# 04__EFR32_Signal_Assign.net
KiCad netlist of a schematic drawn in Altium Designer
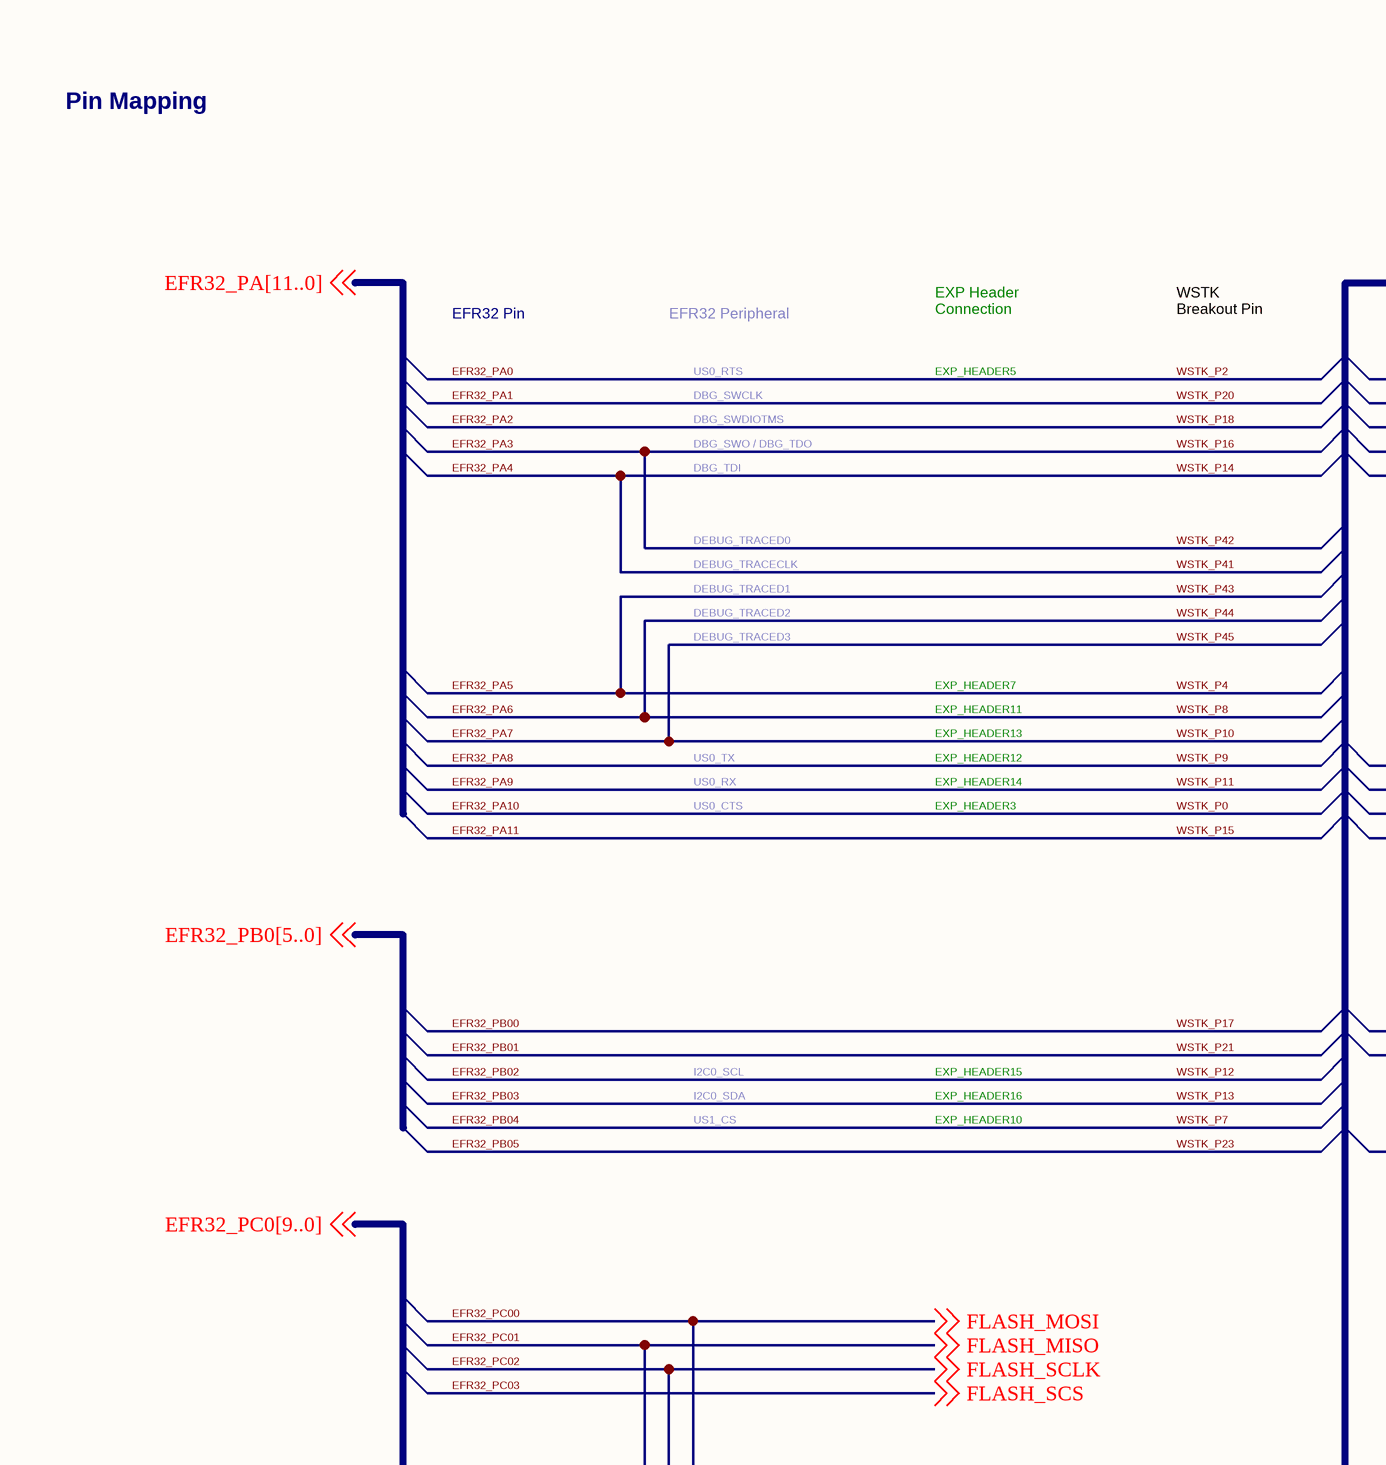
[diagram p0: 04_ EFR32 Signal Assign.SchDoc, top left]
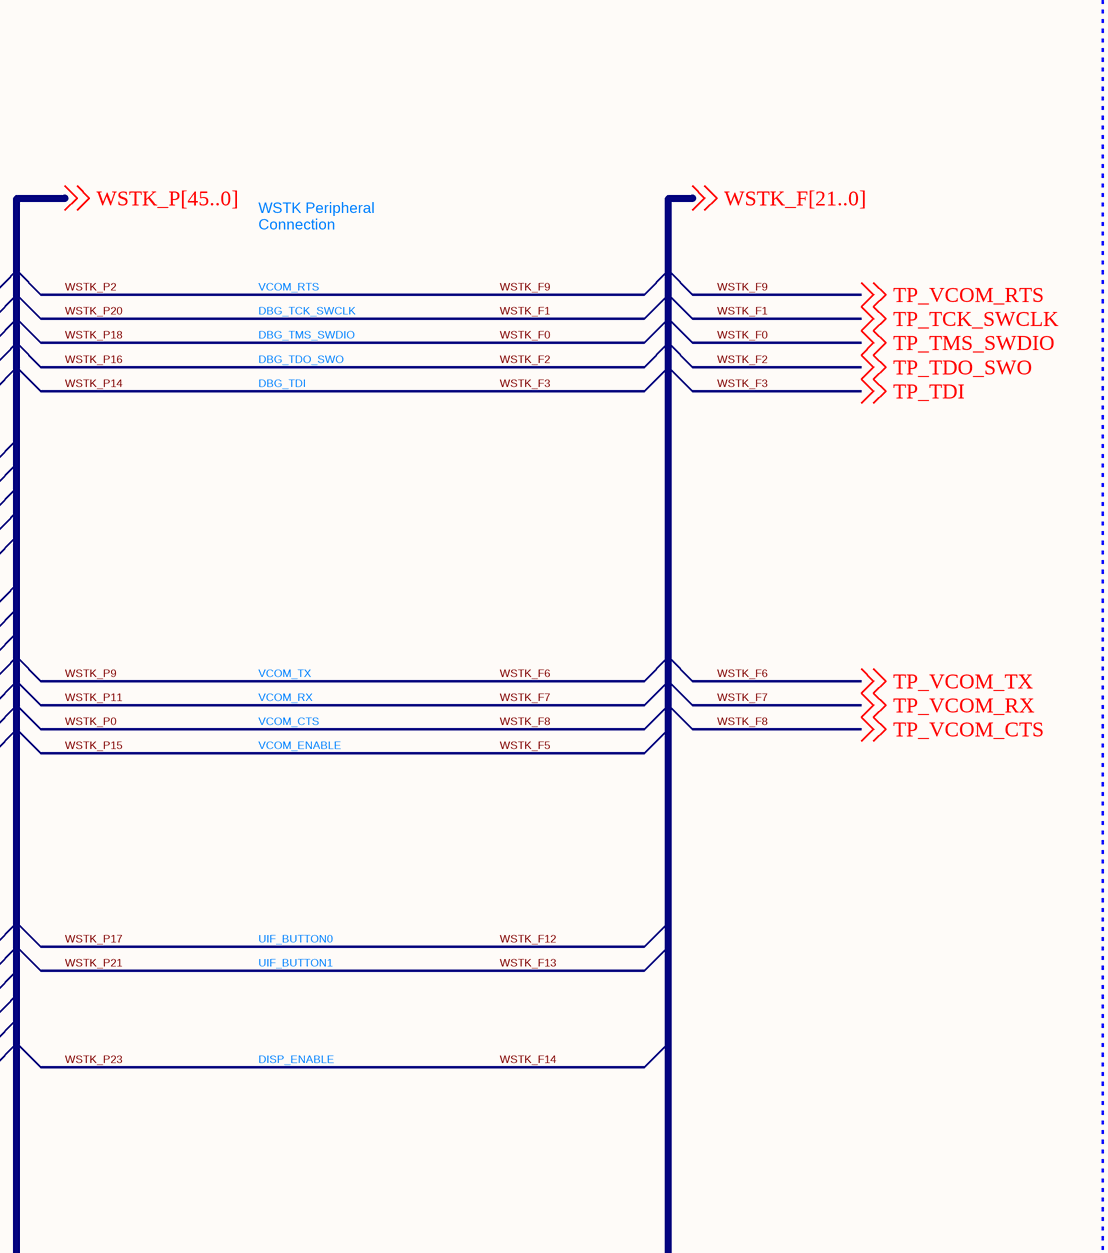
[diagram p1: 04_ EFR32 Signal Assign.SchDoc, top middle]
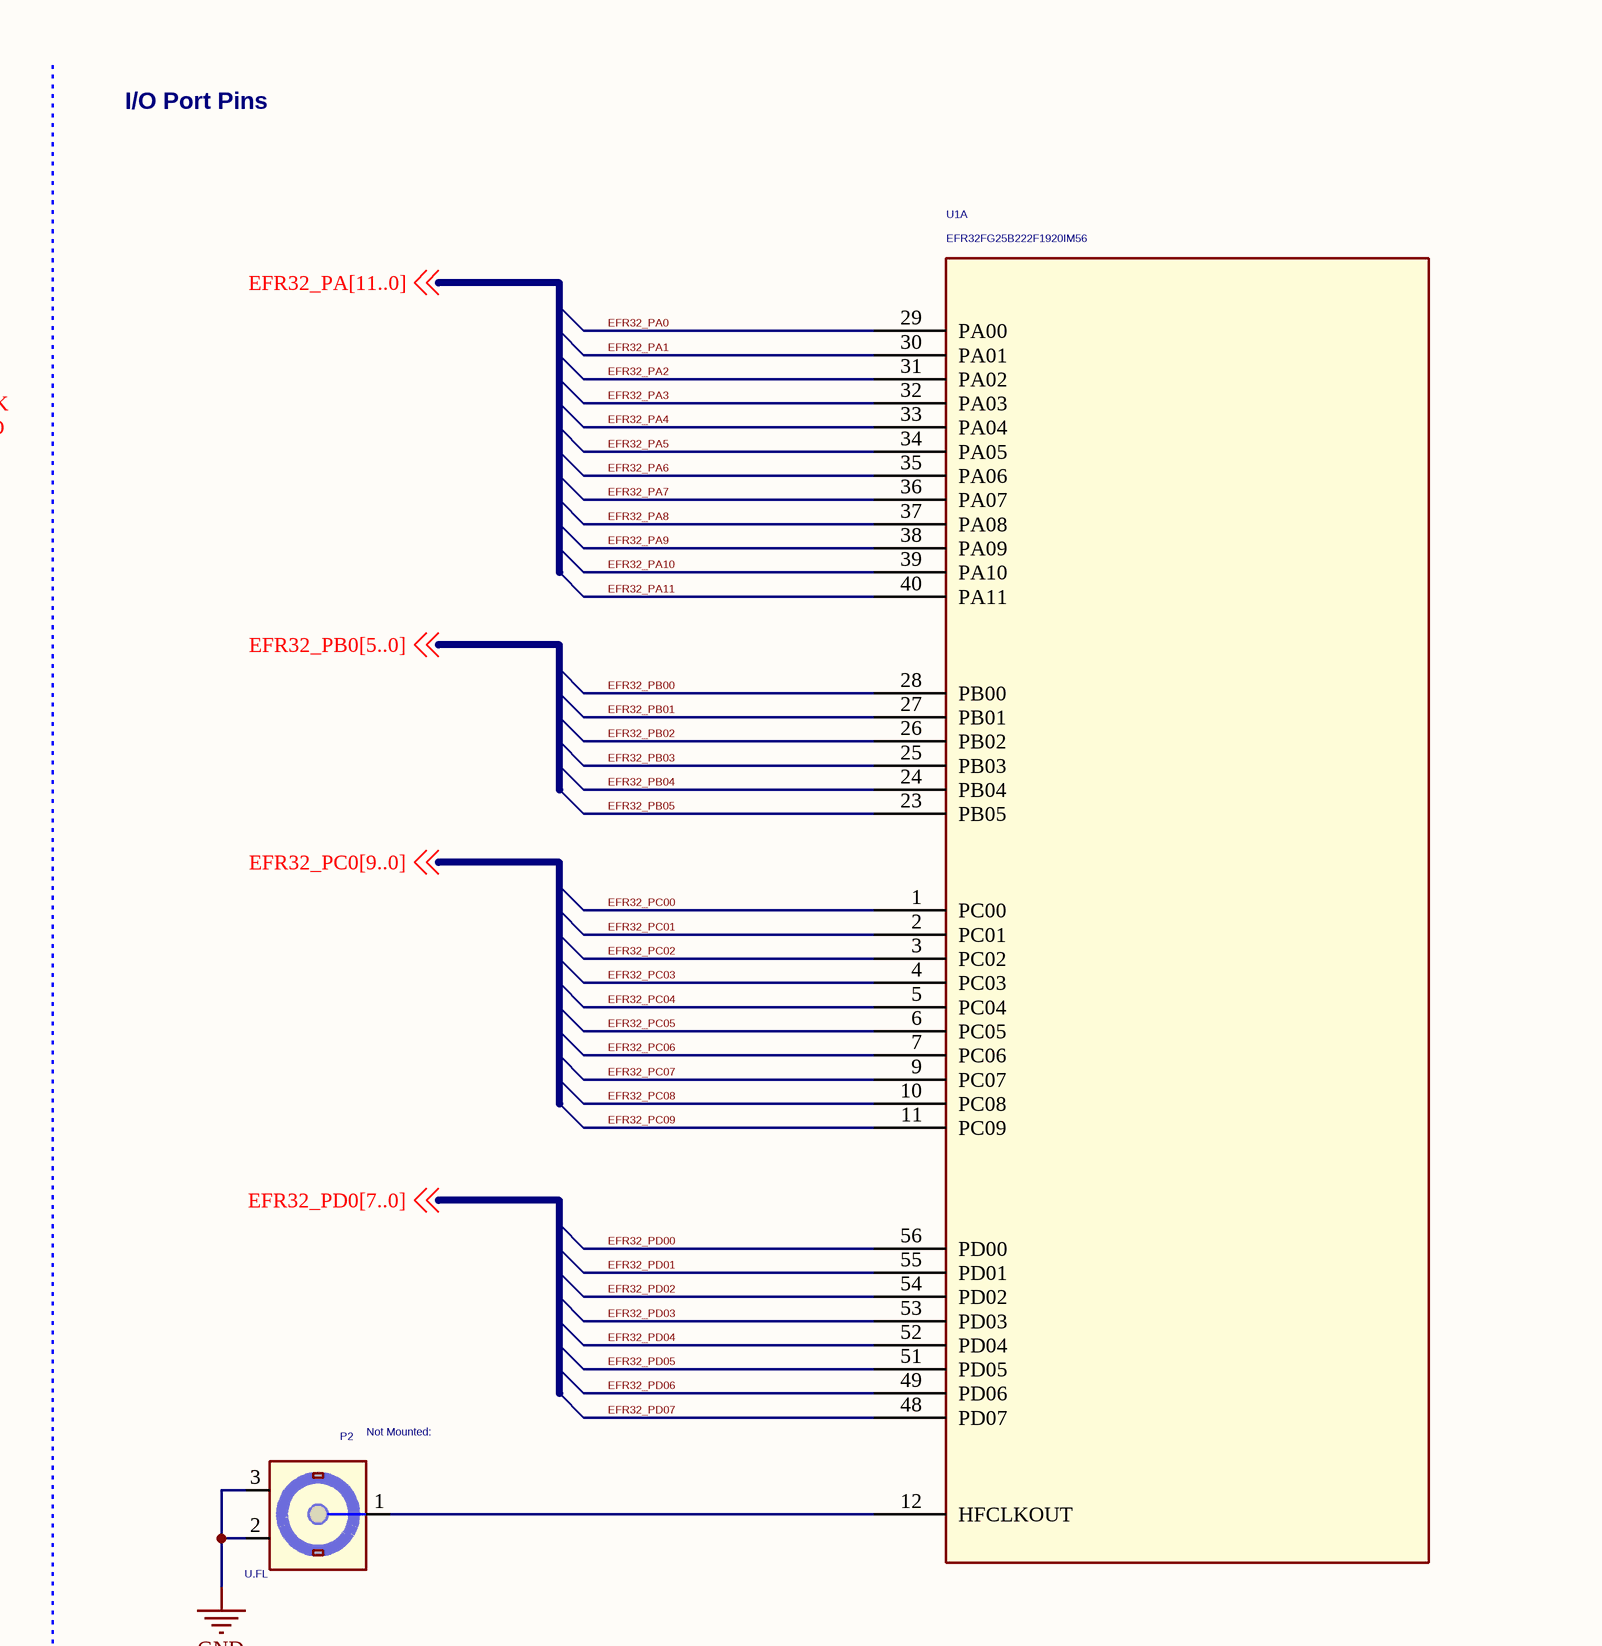
[diagram p2: 04_ EFR32 Signal Assign.SchDoc, top right]
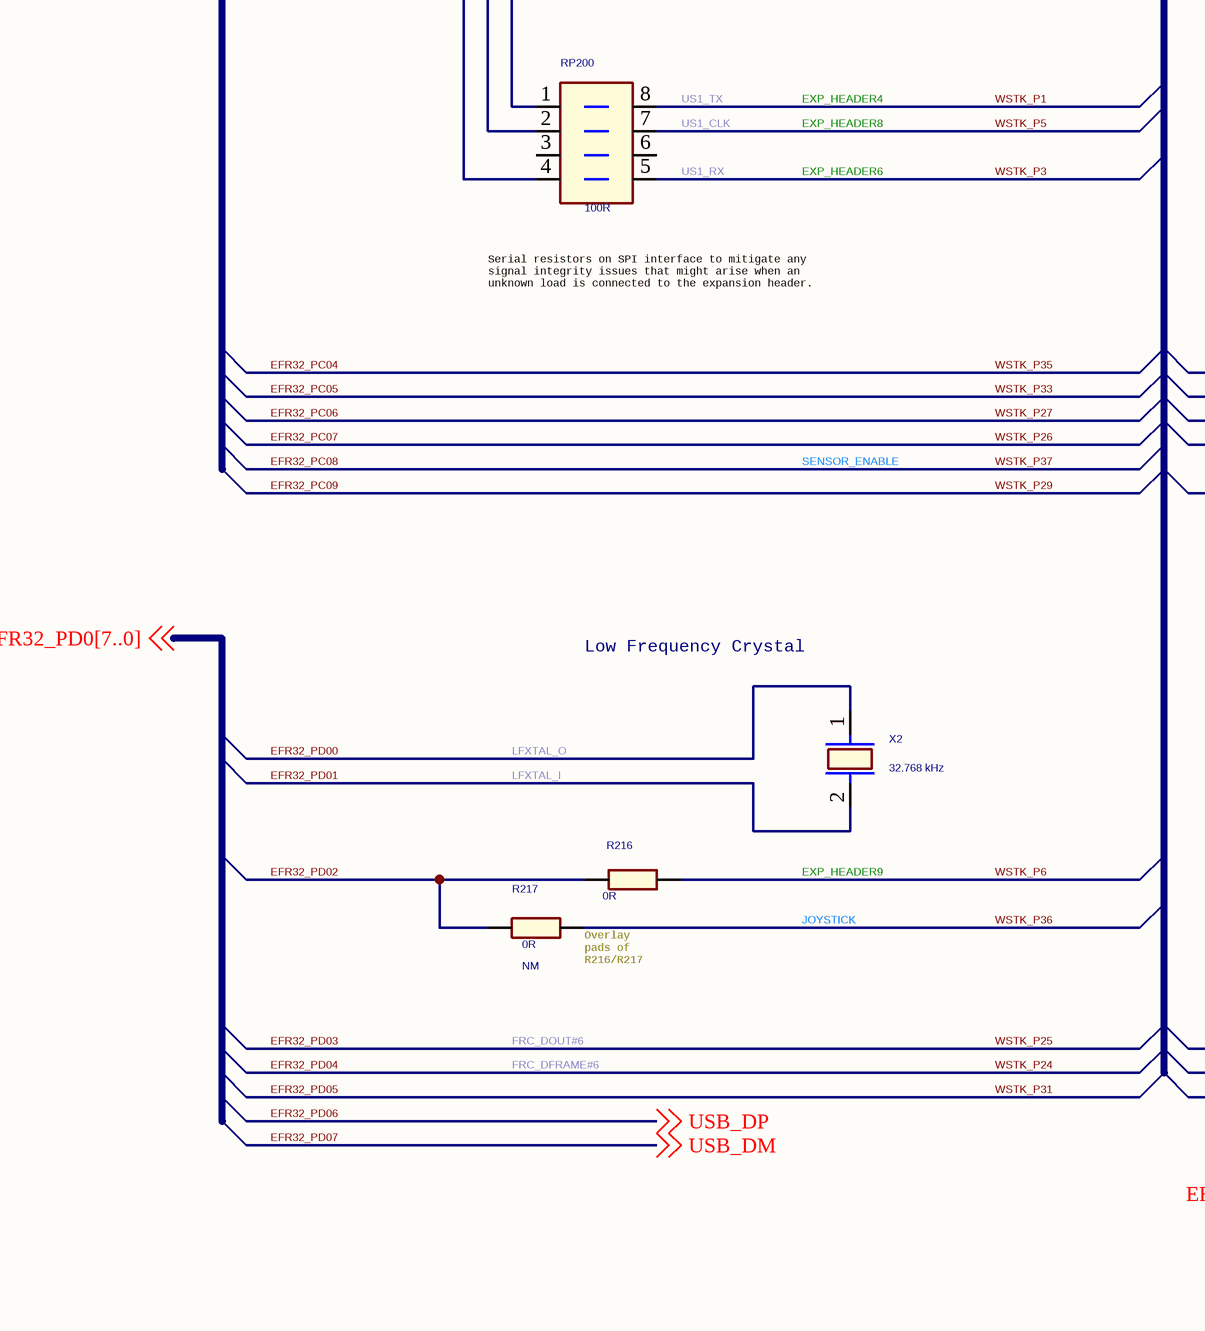
[diagram p3: 04_ EFR32 Signal Assign.SchDoc, bottom left]
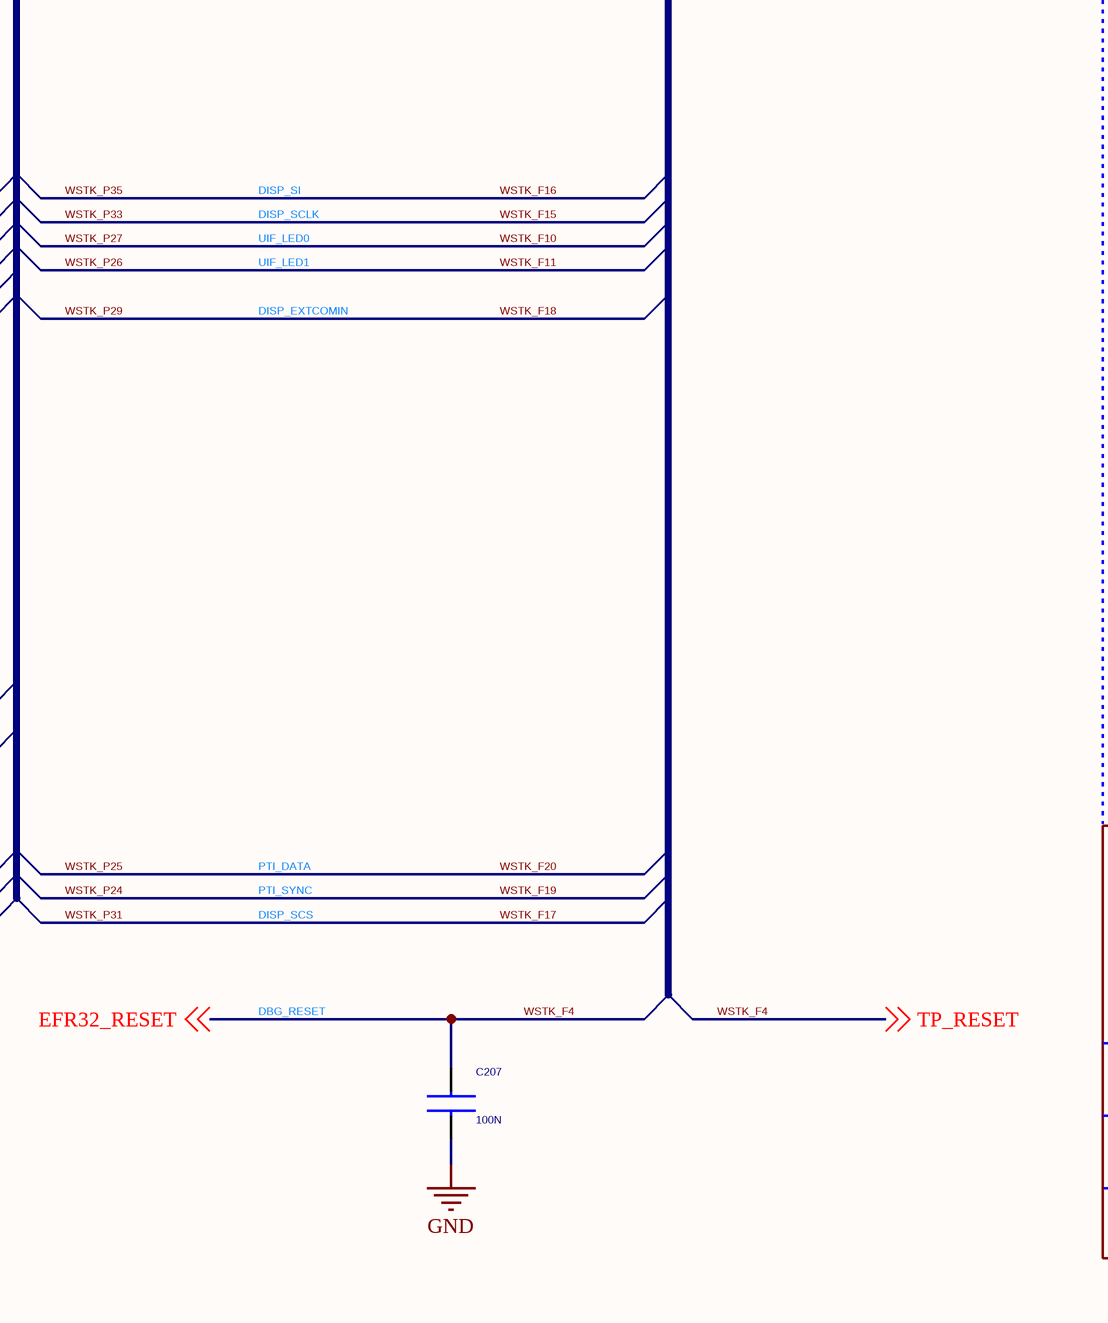
[diagram p4: 04_ EFR32 Signal Assign.SchDoc, bottom middle]
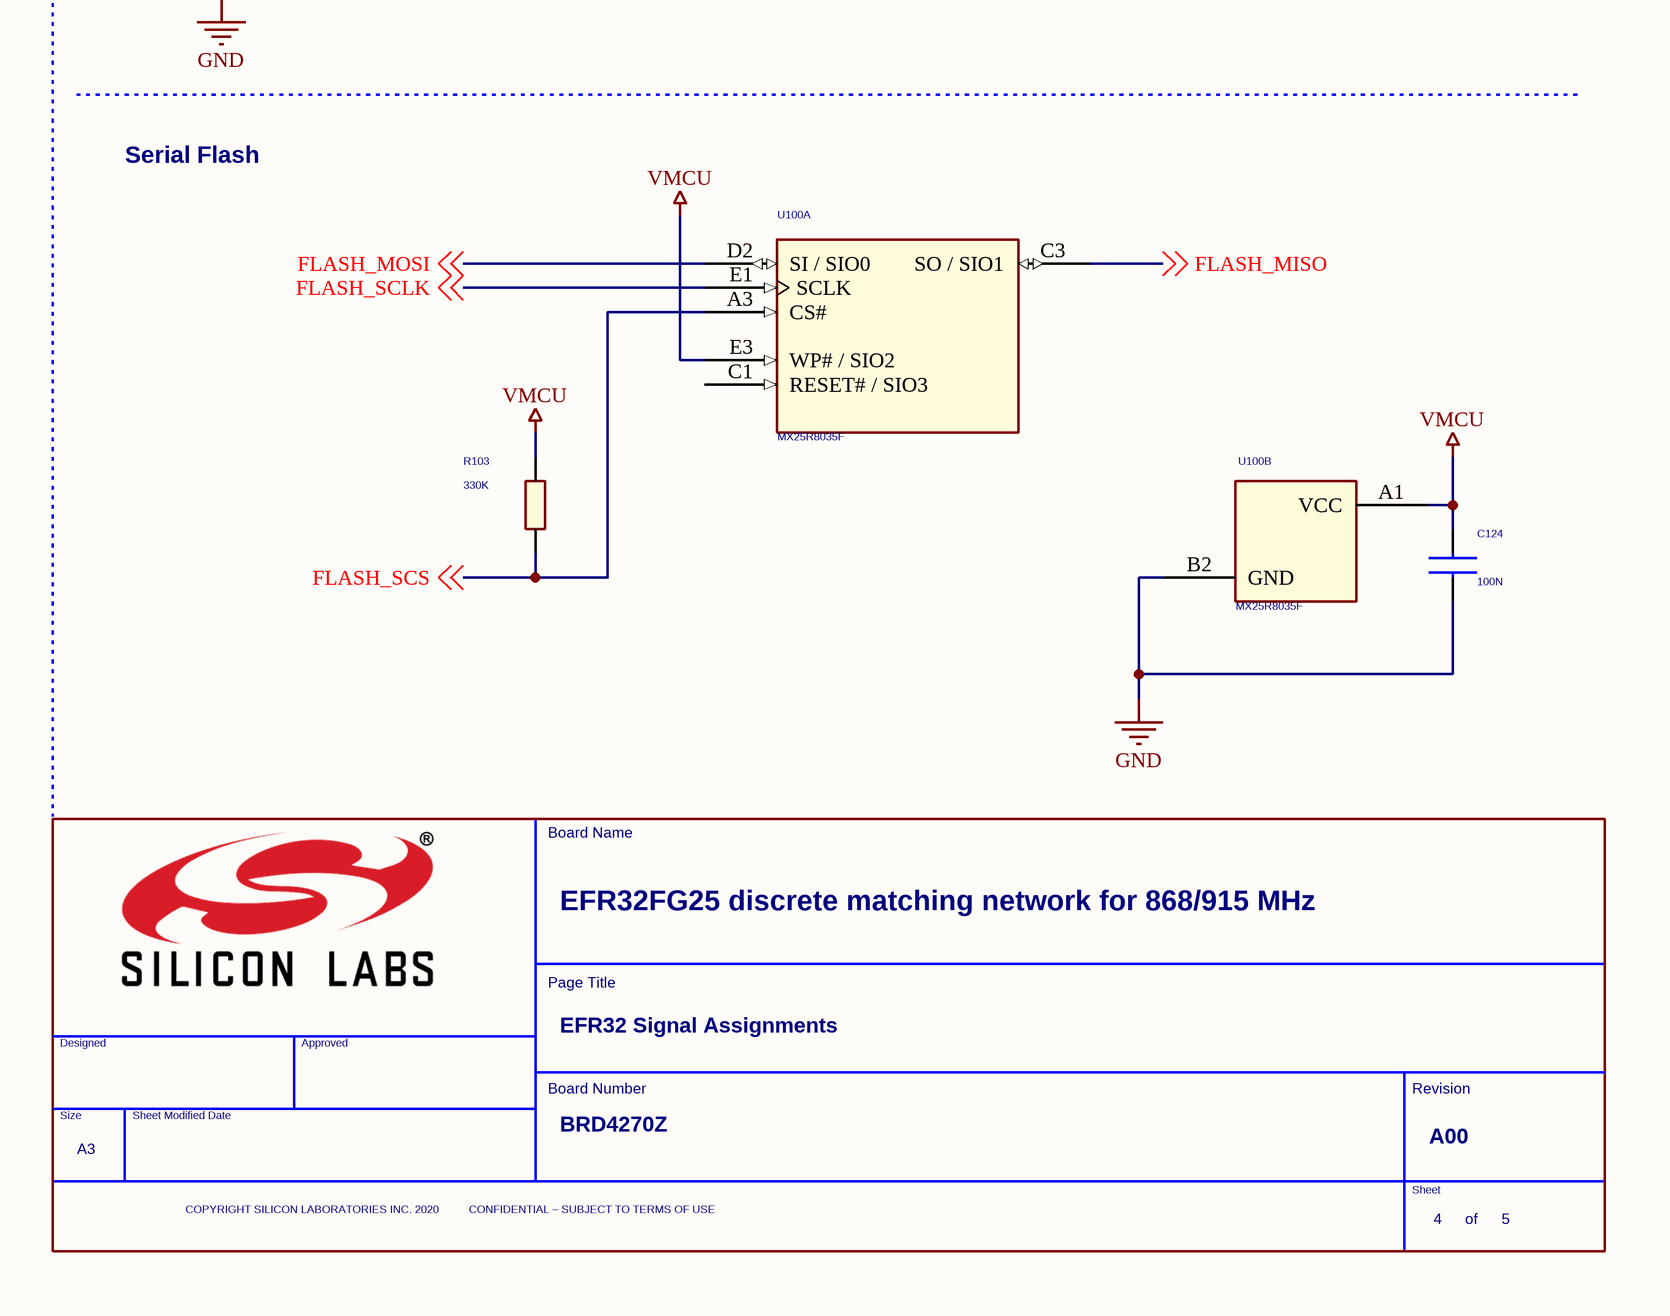
[diagram p5: 04_ EFR32 Signal Assign.SchDoc, bottom right]

(export (version "E")
  (design (tool "Eeschema 10.0.6"))
  (components
    (comp (ref "C124")
      (value "100N")
      (footprint "C0201_L")
      (fields (field (name "TOLERANCE") "20%"))
      (libsource (lib "*") (part "C0201"))
    )
    (comp (ref "C207")
      (value "100N")
      (footprint "C0201_L")
      (fields (field (name "TOLERANCE") "20%"))
      (libsource (lib "*") (part "C0201"))
    )
    (comp (ref "P2")
      (value "U.FL")
      (footprint "HIROSE_U.FL-R-SMT-1")
      (fields (field (name "MFG") "KLS"))
      (libsource (lib "*") (part "KLS_U.FL"))
    )
    (comp (ref "R103") (value "330K") (footprint "R0201_L") (libsource (lib "*") (part "R0201")))
    (comp (ref "R216") (value "0R") (footprint "R0402_L") (libsource (lib "") (part "R0402_1")))
    (comp (ref "R217")
      (value "0R")
      (footprint "R0402_L")
      (fields (field (name "NOT MOUNTED") "NM"))
      (libsource (lib "*") (part "R0402"))
    )
    (comp (ref "RP200")
      (value "100R")
      (footprint "RES_MNR04-8")
      (fields (field (name "MFG") "ROHM"))
      (libsource (lib "*") (part "MNR04M0APJ101"))
    )
    (comp (ref "U1")
      (value "EFR32FG25B222F1920IM56")
      (footprint "QFN56_M040_7.0X7.0_EP_SL")
      (fields (field (name "MFG") "Silicon Labs"))
      (libsource (lib "*") (part "EFR32xG25_QFN56_HFCLKOUT"))
    )
    (comp (ref "U100")
      (value "MX25R8035F")
      (footprint "BGA8_M040_1.24x1.75_WLCSP")
      (fields (field (name "MFG") "Macronix"))
      (libsource (lib "*") (part "MX25R8035"))
    )
    (comp (ref "X2")
      (value "32.768 kHz")
      (footprint "X_MCS_CM8V-T1A")
      (fields (field (name "MFG") "Micro Crystal AG"))
      (libsource (lib "*") (part "CM8V-T1A"))
    )
  )
  (nets
    (net (code "4") (name "EFR32_PD00") (class "Default")
      (node (ref "U1") (pin "56") (pinfunction "PD00_56") (pintype "passive"))
      (node (ref "X2") (pin "1") (pinfunction "1_1") (pintype "passive"))
    )
    (net (code "6") (name "EFR32_PD01") (class "Default")
      (node (ref "U1") (pin "55") (pinfunction "PD01_55") (pintype "passive"))
      (node (ref "X2") (pin "2") (pinfunction "2_2") (pintype "passive"))
    )
    (net (code "7") (name "EFR32_PD02") (class "Default")
      (node (ref "R216") (pin "2") (pinfunction "2_2") (pintype "passive"))
      (node (ref "R217") (pin "1") (pinfunction "1_1") (pintype "passive"))
      (node (ref "U1") (pin "54") (pinfunction "PD02_54") (pintype "passive"))
    )
    (net (code "8") (name "EFR32_PD03") (class "Default")
      (node (ref "U1") (pin "53") (pinfunction "PD03_53") (pintype "passive"))
    )
    (net (code "9") (name "EFR32_PD04") (class "Default")
      (node (ref "U1") (pin "52") (pinfunction "PD04_52") (pintype "passive"))
    )
    (net (code "10") (name "EFR32_PD05") (class "Default")
      (node (ref "U1") (pin "51") (pinfunction "PD05_51") (pintype "passive"))
    )
    (net (code "11") (name "EFR32_RESET") (class "Default")
      (node (ref "C207") (pin "1") (pinfunction "1_1") (pintype "passive"))
    )
    (net (code "12") (name "FLASH_MISO") (class "Default")
      (node (ref "RP200") (pin "4") (pinfunction "R14_4") (pintype "passive"))
      (node (ref "U1") (pin "2") (pinfunction "PC01_2") (pintype "passive"))
      (node (ref "U100") (pin "C3") (pinfunction "SO_/_SIO1_C3") (pintype "bidirectional"))
    )
    (net (code "13") (name "FLASH_MOSI") (class "Default")
      (node (ref "RP200") (pin "1") (pinfunction "R11_1") (pintype "passive"))
      (node (ref "U1") (pin "1") (pinfunction "PC00_1") (pintype "passive"))
      (node (ref "U100") (pin "D2") (pinfunction "SI_/_SIO0_D2") (pintype "bidirectional"))
    )
    (net (code "14") (name "FLASH_SCLK") (class "Default")
      (node (ref "RP200") (pin "2") (pinfunction "R12_2") (pintype "passive"))
      (node (ref "U1") (pin "3") (pinfunction "PC02_3") (pintype "passive"))
      (node (ref "U100") (pin "E1") (pinfunction "SCLK_E1") (pintype "input"))
    )
    (net (code "15") (name "FLASH_SCS") (class "Default")
      (node (ref "R103") (pin "1") (pinfunction "1_1") (pintype "passive"))
      (node (ref "U1") (pin "4") (pinfunction "PC03_4") (pintype "passive"))
      (node (ref "U100") (pin "A3") (pinfunction "CS#_A3") (pintype "input"))
    )
    (net (code "16") (name "GND") (class "Default")
      (node (ref "C124") (pin "2") (pinfunction "2_2") (pintype "passive"))
      (node (ref "C207") (pin "2") (pinfunction "2_2") (pintype "passive"))
      (node (ref "P2") (pin "2") (pinfunction "GND1_2") (pintype "passive"))
      (node (ref "P2") (pin "3") (pinfunction "GND4_3") (pintype "passive"))
      (node (ref "U100") (pin "B2") (pinfunction "GND_B2") (pintype "power_in"))
    )
    (net (code "17") (name "Net-(P2-SIGNAL)") (class "Default")
      (node (ref "P2") (pin "1") (pinfunction "SIGNAL_1") (pintype "passive"))
      (node (ref "U1") (pin "12") (pinfunction "HFCLKOUT_12") (pintype "passive"))
    )
    (net (code "18") (name "TP_TCK_SWCLK") (class "Default")
      (node (ref "U1") (pin "30") (pinfunction "PA01_30") (pintype "passive"))
    )
    (net (code "19") (name "TP_TDI") (class "Default")
      (node (ref "U1") (pin "33") (pinfunction "PA04_33") (pintype "passive"))
    )
    (net (code "20") (name "TP_TDO_SWO") (class "Default")
      (node (ref "U1") (pin "32") (pinfunction "PA03_32") (pintype "passive"))
    )
    (net (code "21") (name "TP_TMS_SWDIO") (class "Default")
      (node (ref "U1") (pin "31") (pinfunction "PA02_31") (pintype "passive"))
    )
    (net (code "22") (name "TP_VCOM_CTS") (class "Default")
      (node (ref "U1") (pin "39") (pinfunction "PA10_39") (pintype "passive"))
    )
    (net (code "23") (name "TP_VCOM_RTS") (class "Default")
      (node (ref "U1") (pin "29") (pinfunction "PA00_29") (pintype "passive"))
    )
    (net (code "24") (name "TP_VCOM_RX") (class "Default")
      (node (ref "U1") (pin "38") (pinfunction "PA09_38") (pintype "passive"))
    )
    (net (code "25") (name "TP_VCOM_TX") (class "Default")
      (node (ref "U1") (pin "37") (pinfunction "PA08_37") (pintype "passive"))
    )
    (net (code "26") (name "USB_DM") (class "Default")
      (node (ref "U1") (pin "48") (pinfunction "PD07_48") (pintype "passive"))
    )
    (net (code "27") (name "USB_DP") (class "Default")
      (node (ref "U1") (pin "49") (pinfunction "PD06_49") (pintype "passive"))
    )
    (net (code "28") (name "VMCU") (class "Default")
      (node (ref "C124") (pin "1") (pinfunction "1_1") (pintype "passive"))
      (node (ref "R103") (pin "2") (pinfunction "2_2") (pintype "passive"))
      (node (ref "U100") (pin "A1") (pinfunction "VCC_A1") (pintype "power_in"))
      (node (ref "U100") (pin "E3") (pinfunction "WP#_/_SIO2_E3") (pintype "input"))
    )
    (net (code "29") (name "WSTK_F5") (class "Default")
      (node (ref "U1") (pin "40") (pinfunction "PA11_40") (pintype "passive"))
    )
    (net (code "30") (name "WSTK_F10") (class "Default")
      (node (ref "U1") (pin "7") (pinfunction "PC06_7") (pintype "passive"))
    )
    (net (code "31") (name "WSTK_F11") (class "Default")
      (node (ref "U1") (pin "9") (pinfunction "PC07_9") (pintype "passive"))
    )
    (net (code "32") (name "WSTK_F12") (class "Default")
      (node (ref "U1") (pin "28") (pinfunction "PB00_28") (pintype "passive"))
    )
    (net (code "33") (name "WSTK_F13") (class "Default")
      (node (ref "U1") (pin "27") (pinfunction "PB01_27") (pintype "passive"))
    )
    (net (code "34") (name "WSTK_F14") (class "Default")
      (node (ref "U1") (pin "23") (pinfunction "PB05_23") (pintype "passive"))
    )
    (net (code "35") (name "WSTK_F15") (class "Default")
      (node (ref "U1") (pin "6") (pinfunction "PC05_6") (pintype "passive"))
    )
    (net (code "36") (name "WSTK_F16") (class "Default")
      (node (ref "U1") (pin "5") (pinfunction "PC04_5") (pintype "passive"))
    )
    (net (code "37") (name "WSTK_F18") (class "Default")
      (node (ref "U1") (pin "11") (pinfunction "PC09_11") (pintype "passive"))
    )
    (net (code "39") (name "WSTK_P1") (class "Default")
      (node (ref "RP200") (pin "8") (pinfunction "R18_8") (pintype "passive"))
    )
    (net (code "40") (name "WSTK_P3") (class "Default")
      (node (ref "RP200") (pin "5") (pinfunction "R15_5") (pintype "passive"))
    )
    (net (code "41") (name "WSTK_P5") (class "Default")
      (node (ref "RP200") (pin "7") (pinfunction "R17_7") (pintype "passive"))
    )
    (net (code "42") (name "WSTK_P6") (class "Default")
      (node (ref "R216") (pin "1") (pinfunction "1_1") (pintype "passive"))
    )
    (net (code "43") (name "WSTK_P7") (class "Default")
      (node (ref "U1") (pin "24") (pinfunction "PB04_24") (pintype "passive"))
    )
    (net (code "44") (name "WSTK_P8") (class "Default")
      (node (ref "U1") (pin "35") (pinfunction "PA06_35") (pintype "passive"))
    )
    (net (code "45") (name "WSTK_P12") (class "Default")
      (node (ref "U1") (pin "26") (pinfunction "PB02_26") (pintype "passive"))
    )
    (net (code "46") (name "WSTK_P13") (class "Default")
      (node (ref "U1") (pin "25") (pinfunction "PB03_25") (pintype "passive"))
    )
    (net (code "47") (name "WSTK_P36") (class "Default")
      (node (ref "R217") (pin "2") (pinfunction "2_2") (pintype "passive"))
    )
    (net (code "48") (name "WSTK_P37") (class "Default")
      (node (ref "U1") (pin "10") (pinfunction "PC08_10") (pintype "passive"))
    )
    (net (code "49") (name "WSTK_P43") (class "Default")
      (node (ref "U1") (pin "34") (pinfunction "PA05_34") (pintype "passive"))
    )
    (net (code "50") (name "WSTK_P45") (class "Default")
      (node (ref "U1") (pin "36") (pinfunction "PA07_36") (pintype "passive"))
    )
    (net (code "52") (name "unconnected-(RP200-R13-Pad3)") (class "Default")
      (node (ref "RP200") (pin "3") (pinfunction "R13_3") (pintype "passive"))
    )
    (net (code "53") (name "unconnected-(RP200-R16-Pad6)") (class "Default")
      (node (ref "RP200") (pin "6") (pinfunction "R16_6") (pintype "passive"))
    )
    (net (code "54") (name "unconnected-(U100A-RESET#_{slash}_SIO3-PadC1)") (class "Default")
      (node (ref "U100") (pin "C1") (pinfunction "RESET#_/_SIO3_C1") (pintype "input"))
    )
  )
)
